# AmpDiferencial.net
KiCad netlist of a schematic drawn in EAGLE
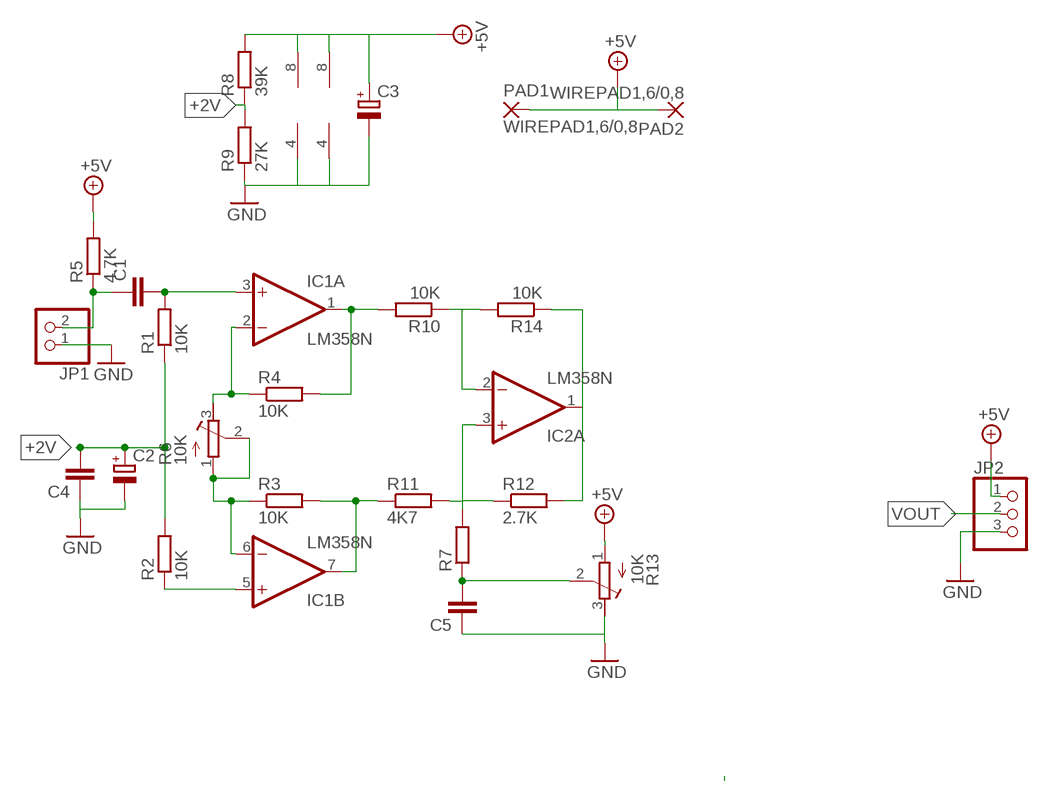
[diagram p0: schematic, sheet 1]

(export (version "E")
  (design (tool "Eeschema 10.0.6"))
  (components
    (comp (ref "C1")
      (value "C-EU050-025X075")
      (footprint "eagle-import:C050-025X075")
      (libsource (lib "eagle-import") (part "resistor_C-EU050-025X075"))
    )
    (comp (ref "C2")
      (value "CPOL-EUE2.5-5")
      (footprint "eagle-import:E2,5-5")
      (libsource (lib "eagle-import") (part "CPOL-EUE2.5-5"))
    )
    (comp (ref "C3")
      (value "CPOL-EUE2.5-6")
      (footprint "eagle-import:E2,5-6")
      (libsource (lib "eagle-import") (part "CPOL-EUE2.5-6"))
    )
    (comp (ref "C4")
      (value "C-EU025-025X050")
      (footprint "eagle-import:C025-025X050")
      (libsource (lib "eagle-import") (part "C-EU025-025X050"))
    )
    (comp (ref "C5")
      (value "C-EU025-025X050")
      (footprint "eagle-import:C025-025X050")
      (libsource (lib "eagle-import") (part "C-EU025-025X050"))
    )
    (comp (ref "IC1")
      (value "LM358N")
      (footprint "eagle-import:DIL08")
      (libsource (lib "eagle-import") (part "LM358N"))
    )
    (comp (ref "IC2")
      (value "LM358N")
      (footprint "eagle-import:DIL08")
      (libsource (lib "eagle-import") (part "LM358N"))
    )
    (comp (ref "JP1")
      (value "PINHD-1X2")
      (footprint "eagle-import:1X02")
      (libsource (lib "eagle-import") (part "PINHD-1X2"))
    )
    (comp (ref "JP2")
      (value "PINHD-1X3")
      (footprint "eagle-import:1X03")
      (libsource (lib "eagle-import") (part "PINHD-1X3"))
    )
    (comp (ref "PAD1")
      (value "WIREPAD1,6/0,8")
      (footprint "eagle-import:1,6_0,8")
      (libsource (lib "eagle-import") (part "WIREPAD1,6/0,8"))
    )
    (comp (ref "PAD2")
      (value "WIREPAD1,6/0,8")
      (footprint "eagle-import:1,6_0,8")
      (libsource (lib "eagle-import") (part "WIREPAD1,6/0,8"))
    )
    (comp (ref "R1")
      (value "10K")
      (footprint "eagle-import:0207_7")
      (libsource (lib "eagle-import") (part "R-EU_0207/7"))
    )
    (comp (ref "R2")
      (value "10K")
      (footprint "eagle-import:0207_7")
      (libsource (lib "eagle-import") (part "R-EU_0207/7"))
    )
    (comp (ref "R3")
      (value "10K")
      (footprint "eagle-import:0207_7")
      (libsource (lib "eagle-import") (part "R-EU_0207/7"))
    )
    (comp (ref "R4")
      (value "10K")
      (footprint "eagle-import:0207_7")
      (libsource (lib "eagle-import") (part "R-EU_0207/7"))
    )
    (comp (ref "R5")
      (value "4.7K")
      (footprint "eagle-import:0207_7")
      (libsource (lib "eagle-import") (part "R-EU_0207/7"))
    )
    (comp (ref "R6")
      (value "10K")
      (footprint "eagle-import:RTRIM64W")
      (libsource (lib "eagle-import") (part "R-TRIMM64W"))
    )
    (comp (ref "R7")
      (value "R-EU_0207/7")
      (footprint "eagle-import:0207_7")
      (libsource (lib "eagle-import") (part "R-EU_0207/7"))
    )
    (comp (ref "R8")
      (value "39K")
      (footprint "eagle-import:0207_7")
      (libsource (lib "eagle-import") (part "R-EU_0207/7"))
    )
    (comp (ref "R9")
      (value "27K")
      (footprint "eagle-import:0207_7")
      (libsource (lib "eagle-import") (part "R-EU_0207/7"))
    )
    (comp (ref "R10")
      (value "10K")
      (footprint "eagle-import:0207_7")
      (libsource (lib "eagle-import") (part "R-EU_0207/7"))
    )
    (comp (ref "R11")
      (value "4K7")
      (footprint "eagle-import:0207_7")
      (libsource (lib "eagle-import") (part "R-EU_0207/7"))
    )
    (comp (ref "R12")
      (value "2.7K")
      (footprint "eagle-import:0207_7")
      (libsource (lib "eagle-import") (part "R-EU_0207/7"))
    )
    (comp (ref "R13")
      (value "10K")
      (footprint "eagle-import:RTRIM64W")
      (libsource (lib "eagle-import") (part "R-TRIMM64W"))
    )
    (comp (ref "R14")
      (value "10K")
      (footprint "eagle-import:0207_7")
      (libsource (lib "eagle-import") (part "R-EU_0207/7"))
    )
  )
  (nets
    (net (code "1") (name "+2V") (class "Default")
      (node (ref "C2") (pin "+") (pinfunction "+_+") (pintype "passive"))
      (node (ref "C4") (pin "2") (pinfunction "2_2") (pintype "passive"))
      (node (ref "R1") (pin "1") (pinfunction "1_1") (pintype "passive"))
      (node (ref "R2") (pin "2") (pinfunction "2_2") (pintype "passive"))
      (node (ref "R8") (pin "1") (pinfunction "1_1") (pintype "passive"))
      (node (ref "R9") (pin "2") (pinfunction "2_2") (pintype "passive"))
    )
    (net (code "2") (name "+5V") (class "Default")
      (node (ref "C3") (pin "+") (pinfunction "+_+") (pintype "passive"))
      (node (ref "IC1") (pin "8") (pinfunction "V+_8") (pintype "power_in"))
      (node (ref "IC2") (pin "8") (pinfunction "V+_8") (pintype "power_in"))
      (node (ref "JP2") (pin "1") (pinfunction "1_1") (pintype "passive"))
      (node (ref "PAD1") (pin "1") (pinfunction "P_1") (pintype "passive"))
      (node (ref "PAD2") (pin "1") (pinfunction "P_1") (pintype "passive"))
      (node (ref "R13") (pin "1") (pinfunction "A_1") (pintype "passive"))
      (node (ref "R5") (pin "2") (pinfunction "2_2") (pintype "passive"))
      (node (ref "R8") (pin "2") (pinfunction "2_2") (pintype "passive"))
    )
    (net (code "3") (name "GND") (class "Default")
      (node (ref "C2") (pin "-") (pinfunction "-_-") (pintype "passive"))
      (node (ref "C3") (pin "-") (pinfunction "-_-") (pintype "passive"))
      (node (ref "C4") (pin "1") (pinfunction "1_1") (pintype "passive"))
      (node (ref "C5") (pin "1") (pinfunction "1_1") (pintype "passive"))
      (node (ref "IC1") (pin "4") (pinfunction "V-_4") (pintype "power_in"))
      (node (ref "IC2") (pin "4") (pinfunction "V-_4") (pintype "power_in"))
      (node (ref "JP1") (pin "1") (pinfunction "1_1") (pintype "passive"))
      (node (ref "JP2") (pin "3") (pinfunction "3_3") (pintype "passive"))
      (node (ref "R13") (pin "3") (pinfunction "E_3") (pintype "passive"))
      (node (ref "R9") (pin "1") (pinfunction "1_1") (pintype "passive"))
    )
    (net (code "4") (name "Net-(C1-Pad1)") (class "Default")
      (node (ref "C1") (pin "1") (pinfunction "1_1") (pintype "passive"))
      (node (ref "JP1") (pin "2") (pinfunction "2_2") (pintype "passive"))
      (node (ref "R5") (pin "1") (pinfunction "1_1") (pintype "passive"))
    )
    (net (code "5") (name "Net-(IC1A-+IN)") (class "Default")
      (node (ref "C1") (pin "2") (pinfunction "2_2") (pintype "passive"))
      (node (ref "IC1") (pin "3") (pinfunction "+IN_3") (pintype "input"))
      (node (ref "R1") (pin "2") (pinfunction "2_2") (pintype "passive"))
    )
    (net (code "6") (name "Net-(IC1A--IN)") (class "Default")
      (node (ref "IC1") (pin "2") (pinfunction "-IN_2") (pintype "input"))
      (node (ref "R4") (pin "1") (pinfunction "1_1") (pintype "passive"))
      (node (ref "R6") (pin "3") (pinfunction "E_3") (pintype "passive"))
    )
    (net (code "7") (name "Net-(IC1A-OUT)") (class "Default")
      (node (ref "IC1") (pin "1") (pinfunction "OUT_1") (pintype "output"))
      (node (ref "R10") (pin "2") (pinfunction "2_2") (pintype "passive"))
      (node (ref "R4") (pin "2") (pinfunction "2_2") (pintype "passive"))
    )
    (net (code "8") (name "Net-(IC1B-+IN)") (class "Default")
      (node (ref "IC1") (pin "5") (pinfunction "+IN_5") (pintype "input"))
      (node (ref "R2") (pin "1") (pinfunction "1_1") (pintype "passive"))
    )
    (net (code "9") (name "Net-(IC1B--IN)") (class "Default")
      (node (ref "IC1") (pin "6") (pinfunction "-IN_6") (pintype "input"))
      (node (ref "R3") (pin "1") (pinfunction "1_1") (pintype "passive"))
      (node (ref "R6") (pin "1") (pinfunction "A_1") (pintype "passive"))
      (node (ref "R6") (pin "2") (pinfunction "S_2") (pintype "passive"))
    )
    (net (code "10") (name "Net-(IC1B-OUT)") (class "Default")
      (node (ref "IC1") (pin "7") (pinfunction "OUT_7") (pintype "output"))
      (node (ref "R11") (pin "1") (pinfunction "1_1") (pintype "passive"))
      (node (ref "R3") (pin "2") (pinfunction "2_2") (pintype "passive"))
    )
    (net (code "11") (name "Net-(IC2A-+IN)") (class "Default")
      (node (ref "IC2") (pin "3") (pinfunction "+IN_3") (pintype "input"))
      (node (ref "R11") (pin "2") (pinfunction "2_2") (pintype "passive"))
      (node (ref "R12") (pin "1") (pinfunction "1_1") (pintype "passive"))
      (node (ref "R7") (pin "2") (pinfunction "2_2") (pintype "passive"))
    )
    (net (code "12") (name "Net-(IC2A--IN)") (class "Default")
      (node (ref "IC2") (pin "2") (pinfunction "-IN_2") (pintype "input"))
      (node (ref "R10") (pin "1") (pinfunction "1_1") (pintype "passive"))
      (node (ref "R14") (pin "2") (pinfunction "2_2") (pintype "passive"))
    )
    (net (code "13") (name "Net-(IC2A-OUT)") (class "Default")
      (node (ref "IC2") (pin "1") (pinfunction "OUT_1") (pintype "output"))
      (node (ref "R12") (pin "2") (pinfunction "2_2") (pintype "passive"))
      (node (ref "R14") (pin "1") (pinfunction "1_1") (pintype "passive"))
    )
    (net (code "14") (name "Net-(R13-S)") (class "Default")
      (node (ref "C5") (pin "2") (pinfunction "2_2") (pintype "passive"))
      (node (ref "R13") (pin "2") (pinfunction "S_2") (pintype "passive"))
      (node (ref "R7") (pin "1") (pinfunction "1_1") (pintype "passive"))
    )
    (net (code "15") (name "VOUT") (class "Default")
      (node (ref "JP2") (pin "2") (pinfunction "2_2") (pintype "passive"))
    )
  )
)
